# ATSAMD21_board.net
KiCad netlist of a schematic drawn in EAGLE
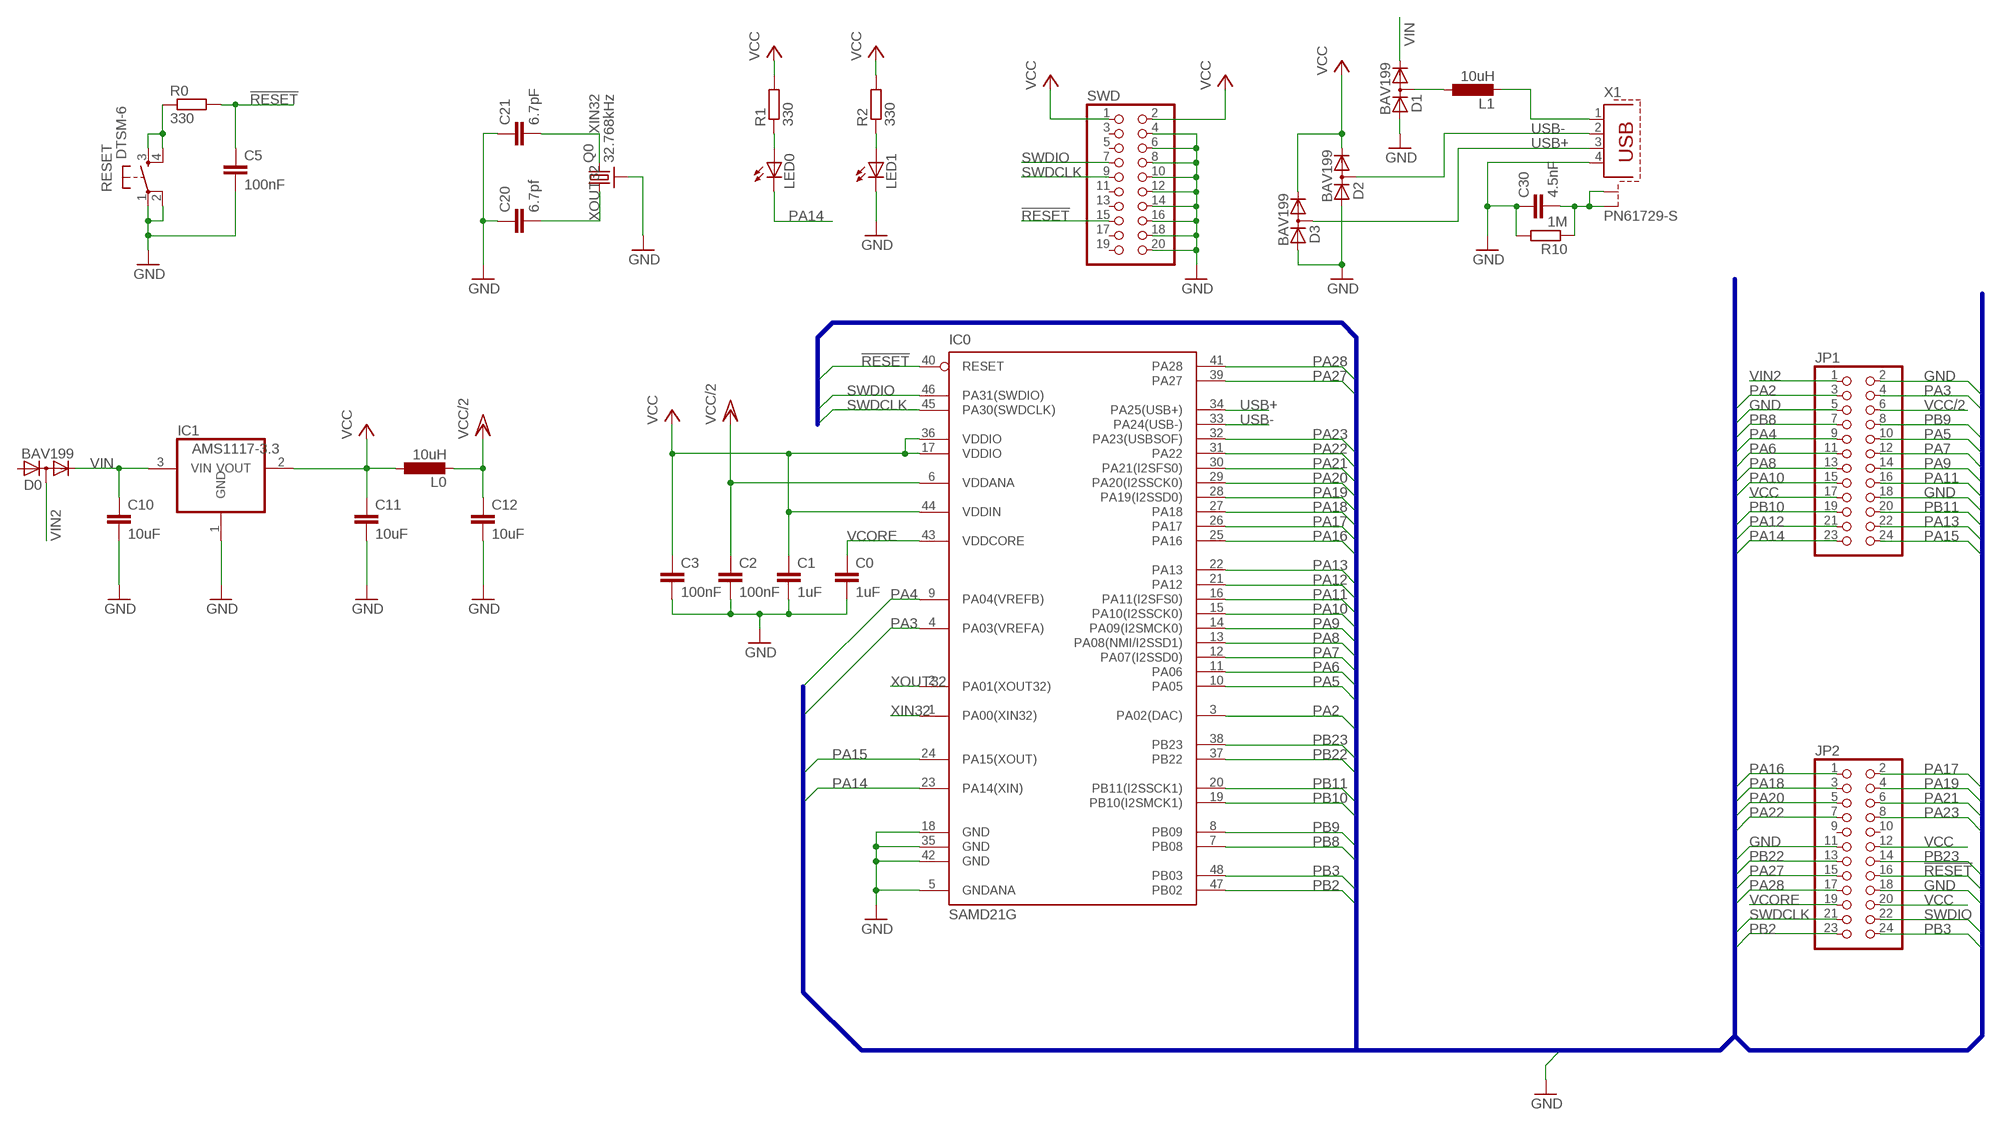
[diagram p0: schematic, sheet 1]

(export (version "E")
  (design (tool "Eeschema 10.0.6"))
  (components
    (comp (ref "C0")
      (value "1uF")
      (footprint "eagle-import:C0805K")
      (libsource (lib "eagle-import") (part "C-EUC0805K"))
    )
    (comp (ref "C1")
      (value "1uF")
      (footprint "eagle-import:C0805K")
      (libsource (lib "eagle-import") (part "C-EUC0805K"))
    )
    (comp (ref "C2")
      (value "100nF")
      (footprint "eagle-import:C0805K")
      (libsource (lib "eagle-import") (part "C-EUC0805K"))
    )
    (comp (ref "C3")
      (value "100nF")
      (footprint "eagle-import:C0805K")
      (libsource (lib "eagle-import") (part "C-EUC0805K"))
    )
    (comp (ref "C5")
      (value "100nF")
      (footprint "eagle-import:C0805K")
      (libsource (lib "eagle-import") (part "C-EUC0805K"))
    )
    (comp (ref "C10")
      (value "10uF")
      (footprint "eagle-import:C0805K")
      (libsource (lib "eagle-import") (part "C-EUC0805K"))
    )
    (comp (ref "C11")
      (value "10uF")
      (footprint "eagle-import:C0805K")
      (libsource (lib "eagle-import") (part "C-EUC0805K"))
    )
    (comp (ref "C12")
      (value "10uF")
      (footprint "eagle-import:C0805K")
      (libsource (lib "eagle-import") (part "C-EUC0805K"))
    )
    (comp (ref "C20")
      (value "6.7pf")
      (footprint "eagle-import:C0805K")
      (libsource (lib "eagle-import") (part "C-EUC0805K"))
    )
    (comp (ref "C21")
      (value "6.7pF")
      (footprint "eagle-import:C0805K")
      (libsource (lib "eagle-import") (part "C-EUC0805K"))
    )
    (comp (ref "C30")
      (value "4.5nF")
      (footprint "eagle-import:C0805K")
      (libsource (lib "eagle-import") (part "C-EUC0805K"))
    )
    (comp (ref "D0")
      (value "BAV199")
      (footprint "eagle-import:SOT23")
      (libsource (lib "eagle-import") (part "BAV199"))
    )
    (comp (ref "D1")
      (value "BAV199")
      (footprint "eagle-import:SOT23")
      (libsource (lib "eagle-import") (part "BAV199"))
    )
    (comp (ref "D2")
      (value "BAV199")
      (footprint "eagle-import:SOT23")
      (libsource (lib "eagle-import") (part "BAV199"))
    )
    (comp (ref "D3")
      (value "BAV199")
      (footprint "eagle-import:SOT23")
      (libsource (lib "eagle-import") (part "BAV199"))
    )
    (comp (ref "IC0")
      (value "SAMD21G")
      (footprint "eagle-import:TQFP48")
      (libsource (lib "eagle-import") (part "SAMD21G"))
    )
    (comp (ref "IC1")
      (value "AMS1117-3.3")
      (footprint "eagle-import:SOT223")
      (fields (field (name "MPN") "REG1117"))
      (libsource (lib "eagle-import") (part "REG1117"))
    )
    (comp (ref "JP1")
      (value "PINHD-2X12")
      (footprint "eagle-import:2X12")
      (libsource (lib "eagle-import") (part "PINHD-2X12"))
    )
    (comp (ref "JP2")
      (value "PINHD-2X12")
      (footprint "eagle-import:2X12")
      (libsource (lib "eagle-import") (part "PINHD-2X12"))
    )
    (comp (ref "L0")
      (value "10uH")
      (footprint "eagle-import:L2012C")
      (libsource (lib "eagle-import") (part "L-EUL2012C"))
    )
    (comp (ref "L1")
      (value "10uH")
      (footprint "eagle-import:L2012C")
      (libsource (lib "eagle-import") (part "L-EUL2012C"))
    )
    (comp (ref "LED0")
      (value "LEDCHIP-LED0805")
      (footprint "eagle-import:CHIP-LED0805")
      (libsource (lib "eagle-import") (part "LEDCHIP-LED0805"))
    )
    (comp (ref "LED1")
      (value "LEDCHIP-LED0805")
      (footprint "eagle-import:CHIP-LED0805")
      (libsource (lib "eagle-import") (part "LEDCHIP-LED0805"))
    )
    (comp (ref "Q0")
      (value "32.768kHz")
      (footprint "eagle-import:TC26H")
      (libsource (lib "eagle-import") (part "CRYSTALTC26H"))
    )
    (comp (ref "R0")
      (value "330")
      (footprint "eagle-import:R0805")
      (libsource (lib "eagle-import") (part "R-EU_R0805"))
    )
    (comp (ref "R1")
      (value "330")
      (footprint "eagle-import:R0805")
      (libsource (lib "eagle-import") (part "R-EU_R0805"))
    )
    (comp (ref "R2")
      (value "330")
      (footprint "eagle-import:R0805")
      (libsource (lib "eagle-import") (part "R-EU_R0805"))
    )
    (comp (ref "R10")
      (value "1M")
      (footprint "eagle-import:R0805")
      (libsource (lib "eagle-import") (part "R-EU_R0805"))
    )
    (comp (ref "RESET")
      (value "DTSM-6")
      (footprint "eagle-import:DTSM-6")
      (libsource (lib "eagle-import") (part "DTSM-6"))
    )
    (comp (ref "SWD")
      (value "PINHD-2X10")
      (footprint "eagle-import:2X10")
      (libsource (lib "eagle-import") (part "PINHD-2X10"))
    )
    (comp (ref "X1")
      (value "PN61729-S")
      (footprint "eagle-import:PN61729-S")
      (libsource (lib "eagle-import") (part "PN61729-S"))
    )
  )
  (nets
    (net (code "1") (name "/PA2") (class "Default")
      (node (ref "IC0") (pin "3") (pinfunction "PA02(DAC)_3") (pintype "bidirectional"))
      (node (ref "JP1") (pin "3") (pinfunction "3_3") (pintype "passive"))
    )
    (net (code "2") (name "/PA3") (class "Default")
      (node (ref "IC0") (pin "4") (pinfunction "PA03(VREFA)_4") (pintype "bidirectional"))
      (node (ref "JP1") (pin "4") (pinfunction "4_4") (pintype "passive"))
    )
    (net (code "3") (name "/PA4") (class "Default")
      (node (ref "IC0") (pin "9") (pinfunction "PA04(VREFB)_9") (pintype "bidirectional"))
      (node (ref "JP1") (pin "9") (pinfunction "9_9") (pintype "passive"))
    )
    (net (code "4") (name "/PA5") (class "Default")
      (node (ref "IC0") (pin "10") (pinfunction "PA05_10") (pintype "bidirectional"))
      (node (ref "JP1") (pin "10") (pinfunction "10_10") (pintype "passive"))
    )
    (net (code "5") (name "/PA6") (class "Default")
      (node (ref "IC0") (pin "11") (pinfunction "PA06_11") (pintype "bidirectional"))
      (node (ref "JP1") (pin "11") (pinfunction "11_11") (pintype "passive"))
    )
    (net (code "6") (name "/PA7") (class "Default")
      (node (ref "IC0") (pin "12") (pinfunction "PA07(I2SSD0)_12") (pintype "bidirectional"))
      (node (ref "JP1") (pin "12") (pinfunction "12_12") (pintype "passive"))
    )
    (net (code "7") (name "/PA8") (class "Default")
      (node (ref "IC0") (pin "13") (pinfunction "PA08(NMI/I2SSD1)_13") (pintype "bidirectional"))
      (node (ref "JP1") (pin "13") (pinfunction "13_13") (pintype "passive"))
    )
    (net (code "8") (name "/PA9") (class "Default")
      (node (ref "IC0") (pin "14") (pinfunction "PA09(I2SMCK0)_14") (pintype "bidirectional"))
      (node (ref "JP1") (pin "14") (pinfunction "14_14") (pintype "passive"))
    )
    (net (code "9") (name "/PA10") (class "Default")
      (node (ref "IC0") (pin "15") (pinfunction "PA10(I2SSCK0)_15") (pintype "bidirectional"))
      (node (ref "JP1") (pin "15") (pinfunction "15_15") (pintype "passive"))
    )
    (net (code "10") (name "/PA11") (class "Default")
      (node (ref "IC0") (pin "16") (pinfunction "PA11(I2SFS0)_16") (pintype "bidirectional"))
      (node (ref "JP1") (pin "16") (pinfunction "16_16") (pintype "passive"))
    )
    (net (code "11") (name "/PA12") (class "Default")
      (node (ref "IC0") (pin "21") (pinfunction "PA12_21") (pintype "bidirectional"))
      (node (ref "JP1") (pin "21") (pinfunction "21_21") (pintype "passive"))
    )
    (net (code "12") (name "/PA13") (class "Default")
      (node (ref "IC0") (pin "22") (pinfunction "PA13_22") (pintype "bidirectional"))
      (node (ref "JP1") (pin "22") (pinfunction "22_22") (pintype "passive"))
    )
    (net (code "13") (name "/PA14") (class "Default")
      (node (ref "IC0") (pin "23") (pinfunction "PA14(XIN)_23") (pintype "bidirectional"))
      (node (ref "JP1") (pin "23") (pinfunction "23_23") (pintype "passive"))
      (node (ref "LED0") (pin "C") (pinfunction "C_C") (pintype "passive"))
    )
    (net (code "14") (name "/PA15") (class "Default")
      (node (ref "IC0") (pin "24") (pinfunction "PA15(XOUT)_24") (pintype "bidirectional"))
      (node (ref "JP1") (pin "24") (pinfunction "24_24") (pintype "passive"))
    )
    (net (code "15") (name "/PA16") (class "Default")
      (node (ref "IC0") (pin "25") (pinfunction "PA16_25") (pintype "bidirectional"))
      (node (ref "JP2") (pin "1") (pinfunction "1_1") (pintype "passive"))
    )
    (net (code "16") (name "/PA17") (class "Default")
      (node (ref "IC0") (pin "26") (pinfunction "PA17_26") (pintype "bidirectional"))
      (node (ref "JP2") (pin "2") (pinfunction "2_2") (pintype "passive"))
    )
    (net (code "17") (name "/PA18") (class "Default")
      (node (ref "IC0") (pin "27") (pinfunction "PA18_27") (pintype "bidirectional"))
      (node (ref "JP2") (pin "3") (pinfunction "3_3") (pintype "passive"))
    )
    (net (code "18") (name "/PA19") (class "Default")
      (node (ref "IC0") (pin "28") (pinfunction "PA19(I2SSD0)_28") (pintype "bidirectional"))
      (node (ref "JP2") (pin "4") (pinfunction "4_4") (pintype "passive"))
    )
    (net (code "19") (name "/PA20") (class "Default")
      (node (ref "IC0") (pin "29") (pinfunction "PA20(I2SSCK0)_29") (pintype "bidirectional"))
      (node (ref "JP2") (pin "5") (pinfunction "5_5") (pintype "passive"))
    )
    (net (code "20") (name "/PA21") (class "Default")
      (node (ref "IC0") (pin "30") (pinfunction "PA21(I2SFS0)_30") (pintype "bidirectional"))
      (node (ref "JP2") (pin "6") (pinfunction "6_6") (pintype "passive"))
    )
    (net (code "21") (name "/PA22") (class "Default")
      (node (ref "IC0") (pin "31") (pinfunction "PA22_31") (pintype "bidirectional"))
      (node (ref "JP2") (pin "7") (pinfunction "7_7") (pintype "passive"))
    )
    (net (code "22") (name "/PA23") (class "Default")
      (node (ref "IC0") (pin "32") (pinfunction "PA23(USBSOF)_32") (pintype "bidirectional"))
      (node (ref "JP2") (pin "8") (pinfunction "8_8") (pintype "passive"))
    )
    (net (code "23") (name "/PA27") (class "Default")
      (node (ref "IC0") (pin "39") (pinfunction "PA27_39") (pintype "bidirectional"))
      (node (ref "JP2") (pin "15") (pinfunction "15_15") (pintype "passive"))
    )
    (net (code "24") (name "/PA28") (class "Default")
      (node (ref "IC0") (pin "41") (pinfunction "PA28_41") (pintype "bidirectional"))
      (node (ref "JP2") (pin "17") (pinfunction "17_17") (pintype "passive"))
    )
    (net (code "25") (name "/PB2") (class "Default")
      (node (ref "IC0") (pin "47") (pinfunction "PB02_47") (pintype "bidirectional"))
      (node (ref "JP2") (pin "23") (pinfunction "23_23") (pintype "passive"))
    )
    (net (code "26") (name "/PB3") (class "Default")
      (node (ref "IC0") (pin "48") (pinfunction "PB03_48") (pintype "bidirectional"))
      (node (ref "JP2") (pin "24") (pinfunction "24_24") (pintype "passive"))
    )
    (net (code "27") (name "/PB8") (class "Default")
      (node (ref "IC0") (pin "7") (pinfunction "PB08_7") (pintype "bidirectional"))
      (node (ref "JP1") (pin "7") (pinfunction "7_7") (pintype "passive"))
    )
    (net (code "28") (name "/PB9") (class "Default")
      (node (ref "IC0") (pin "8") (pinfunction "PB09_8") (pintype "bidirectional"))
      (node (ref "JP1") (pin "8") (pinfunction "8_8") (pintype "passive"))
    )
    (net (code "29") (name "/PB10") (class "Default")
      (node (ref "IC0") (pin "19") (pinfunction "PB10(I2SMCK1)_19") (pintype "bidirectional"))
      (node (ref "JP1") (pin "19") (pinfunction "19_19") (pintype "passive"))
    )
    (net (code "30") (name "/PB11") (class "Default")
      (node (ref "IC0") (pin "20") (pinfunction "PB11(I2SSCK1)_20") (pintype "bidirectional"))
      (node (ref "JP1") (pin "20") (pinfunction "20_20") (pintype "passive"))
    )
    (net (code "31") (name "/PB22") (class "Default")
      (node (ref "IC0") (pin "37") (pinfunction "PB22_37") (pintype "bidirectional"))
      (node (ref "JP2") (pin "13") (pinfunction "13_13") (pintype "passive"))
    )
    (net (code "32") (name "/PB23") (class "Default")
      (node (ref "IC0") (pin "38") (pinfunction "PB23_38") (pintype "bidirectional"))
      (node (ref "JP2") (pin "14") (pinfunction "14_14") (pintype "passive"))
    )
    (net (code "33") (name "/SWDCLK") (class "Default")
      (node (ref "IC0") (pin "45") (pinfunction "PA30(SWDCLK)_45") (pintype "bidirectional"))
      (node (ref "JP2") (pin "21") (pinfunction "21_21") (pintype "passive"))
      (node (ref "SWD") (pin "9") (pinfunction "9_9") (pintype "passive"))
    )
    (net (code "34") (name "/SWDIO") (class "Default")
      (node (ref "IC0") (pin "46") (pinfunction "PA31(SWDIO)_46") (pintype "bidirectional"))
      (node (ref "JP2") (pin "22") (pinfunction "22_22") (pintype "passive"))
      (node (ref "SWD") (pin "7") (pinfunction "7_7") (pintype "passive"))
    )
    (net (code "35") (name "/USB+") (class "Default")
      (node (ref "D3") (pin "3") (pinfunction "AC_3") (pintype "passive"))
      (node (ref "IC0") (pin "34") (pinfunction "PA25(USB+)_34") (pintype "bidirectional"))
      (node (ref "X1") (pin "3") (pinfunction "3_3") (pintype "passive"))
    )
    (net (code "36") (name "/USB-") (class "Default")
      (node (ref "D2") (pin "3") (pinfunction "AC_3") (pintype "passive"))
      (node (ref "IC0") (pin "33") (pinfunction "PA24(USB-)_33") (pintype "bidirectional"))
      (node (ref "X1") (pin "2") (pinfunction "2_2") (pintype "passive"))
    )
    (net (code "37") (name "/VCORE") (class "Default")
      (node (ref "C0") (pin "1") (pinfunction "1_1") (pintype "passive"))
      (node (ref "IC0") (pin "43") (pinfunction "VDDCORE_43") (pintype "power_in"))
      (node (ref "JP2") (pin "19") (pinfunction "19_19") (pintype "passive"))
    )
    (net (code "38") (name "/VIN") (class "Default")
      (node (ref "C10") (pin "1") (pinfunction "1_1") (pintype "passive"))
      (node (ref "D0") (pin "2") (pinfunction "C_2") (pintype "passive"))
      (node (ref "D1") (pin "2") (pinfunction "C_2") (pintype "passive"))
      (node (ref "IC1") (pin "3") (pinfunction "VIN_3") (pintype "input"))
    )
    (net (code "39") (name "/VIN2") (class "Default")
      (node (ref "D0") (pin "3") (pinfunction "AC_3") (pintype "passive"))
      (node (ref "JP1") (pin "1") (pinfunction "1_1") (pintype "passive"))
    )
    (net (code "40") (name "/XIN32") (class "Default")
      (node (ref "C21") (pin "2") (pinfunction "2_2") (pintype "passive"))
      (node (ref "IC0") (pin "1") (pinfunction "PA00(XIN32)_1") (pintype "bidirectional"))
      (node (ref "Q0") (pin "2") (pinfunction "2_2") (pintype "passive"))
    )
    (net (code "41") (name "/XOUT32") (class "Default")
      (node (ref "C20") (pin "2") (pinfunction "2_2") (pintype "passive"))
      (node (ref "IC0") (pin "2") (pinfunction "PA01(XOUT32)_2") (pintype "bidirectional"))
      (node (ref "Q0") (pin "1") (pinfunction "1_1") (pintype "passive"))
    )
    (net (code "42") (name "/~{RESET}") (class "Default")
      (node (ref "C5") (pin "1") (pinfunction "1_1") (pintype "passive"))
      (node (ref "IC0") (pin "40") (pinfunction "RESET_40") (pintype "bidirectional"))
      (node (ref "JP2") (pin "16") (pinfunction "16_16") (pintype "passive"))
      (node (ref "R0") (pin "2") (pinfunction "2_2") (pintype "passive"))
      (node (ref "SWD") (pin "15") (pinfunction "15_15") (pintype "passive"))
    )
    (net (code "43") (name "GND") (class "Default")
      (node (ref "C0") (pin "2") (pinfunction "2_2") (pintype "passive"))
      (node (ref "C1") (pin "2") (pinfunction "2_2") (pintype "passive"))
      (node (ref "C10") (pin "2") (pinfunction "2_2") (pintype "passive"))
      (node (ref "C11") (pin "2") (pinfunction "2_2") (pintype "passive"))
      (node (ref "C12") (pin "2") (pinfunction "2_2") (pintype "passive"))
      (node (ref "C2") (pin "2") (pinfunction "2_2") (pintype "passive"))
      (node (ref "C20") (pin "1") (pinfunction "1_1") (pintype "passive"))
      (node (ref "C21") (pin "1") (pinfunction "1_1") (pintype "passive"))
      (node (ref "C3") (pin "2") (pinfunction "2_2") (pintype "passive"))
      (node (ref "C30") (pin "1") (pinfunction "1_1") (pintype "passive"))
      (node (ref "C5") (pin "2") (pinfunction "2_2") (pintype "passive"))
      (node (ref "D1") (pin "1") (pinfunction "A_1") (pintype "passive"))
      (node (ref "D2") (pin "1") (pinfunction "A_1") (pintype "passive"))
      (node (ref "D3") (pin "1") (pinfunction "A_1") (pintype "passive"))
      (node (ref "IC0") (pin "18") (pinfunction "GND_18") (pintype "power_in"))
      (node (ref "IC0") (pin "35") (pinfunction "GND_35") (pintype "power_in"))
      (node (ref "IC0") (pin "42") (pinfunction "GND_42") (pintype "power_in"))
      (node (ref "IC0") (pin "5") (pinfunction "GNDANA_5") (pintype "power_in"))
      (node (ref "IC1") (pin "1") (pinfunction "GND_1") (pintype "power_in"))
      (node (ref "JP1") (pin "18") (pinfunction "18_18") (pintype "passive"))
      (node (ref "JP1") (pin "2") (pinfunction "2_2") (pintype "passive"))
      (node (ref "JP1") (pin "5") (pinfunction "5_5") (pintype "passive"))
      (node (ref "JP2") (pin "11") (pinfunction "11_11") (pintype "passive"))
      (node (ref "JP2") (pin "18") (pinfunction "18_18") (pintype "passive"))
      (node (ref "LED1") (pin "C") (pinfunction "C_C") (pintype "passive"))
      (node (ref "Q0") (pin "P$1") (pinfunction "3_P$1") (pintype "passive"))
      (node (ref "R10") (pin "2") (pinfunction "2_2") (pintype "passive"))
      (node (ref "RESET") (pin "1") (pinfunction "1_1") (pintype "passive"))
      (node (ref "RESET") (pin "2") (pinfunction "2_2") (pintype "passive"))
      (node (ref "SWD") (pin "10") (pinfunction "10_10") (pintype "passive"))
      (node (ref "SWD") (pin "12") (pinfunction "12_12") (pintype "passive"))
      (node (ref "SWD") (pin "14") (pinfunction "14_14") (pintype "passive"))
      (node (ref "SWD") (pin "16") (pinfunction "16_16") (pintype "passive"))
      (node (ref "SWD") (pin "18") (pinfunction "18_18") (pintype "passive"))
      (node (ref "SWD") (pin "20") (pinfunction "20_20") (pintype "passive"))
      (node (ref "SWD") (pin "4") (pinfunction "4_4") (pintype "passive"))
      (node (ref "SWD") (pin "6") (pinfunction "6_6") (pintype "passive"))
      (node (ref "SWD") (pin "8") (pinfunction "8_8") (pintype "passive"))
      (node (ref "X1") (pin "4") (pinfunction "4_4") (pintype "passive"))
    )
    (net (code "44") (name "Net-(C30-Pad2)") (class "Default")
      (node (ref "C30") (pin "2") (pinfunction "2_2") (pintype "passive"))
      (node (ref "R10") (pin "1") (pinfunction "1_1") (pintype "passive"))
      (node (ref "X1") (pin "S1") (pinfunction "S1_S1") (pintype "passive"))
      (node (ref "X1") (pin "S2") (pinfunction "S2_S2") (pintype "passive"))
    )
    (net (code "45") (name "Net-(D1-AC)") (class "Default")
      (node (ref "D1") (pin "3") (pinfunction "AC_3") (pintype "passive"))
      (node (ref "L1") (pin "1") (pinfunction "1_1") (pintype "passive"))
    )
    (net (code "46") (name "Net-(L1-Pad2)") (class "Default")
      (node (ref "L1") (pin "2") (pinfunction "2_2") (pintype "passive"))
      (node (ref "X1") (pin "1") (pinfunction "1_1") (pintype "passive"))
    )
    (net (code "47") (name "Net-(LED0-PadA)") (class "Default")
      (node (ref "LED0") (pin "A") (pinfunction "A_A") (pintype "passive"))
      (node (ref "R1") (pin "1") (pinfunction "1_1") (pintype "passive"))
    )
    (net (code "48") (name "Net-(LED1-PadA)") (class "Default")
      (node (ref "LED1") (pin "A") (pinfunction "A_A") (pintype "passive"))
      (node (ref "R2") (pin "1") (pinfunction "1_1") (pintype "passive"))
    )
    (net (code "49") (name "Net-(R0-Pad1)") (class "Default")
      (node (ref "R0") (pin "1") (pinfunction "1_1") (pintype "passive"))
      (node (ref "RESET") (pin "3") (pinfunction "3_3") (pintype "passive"))
      (node (ref "RESET") (pin "4") (pinfunction "4_4") (pintype "passive"))
    )
    (net (code "50") (name "VCC") (class "Default")
      (node (ref "C1") (pin "1") (pinfunction "1_1") (pintype "passive"))
      (node (ref "C11") (pin "1") (pinfunction "1_1") (pintype "passive"))
      (node (ref "C3") (pin "1") (pinfunction "1_1") (pintype "passive"))
      (node (ref "D2") (pin "2") (pinfunction "C_2") (pintype "passive"))
      (node (ref "D3") (pin "2") (pinfunction "C_2") (pintype "passive"))
      (node (ref "IC0") (pin "17") (pinfunction "VDDIO_17") (pintype "power_in"))
      (node (ref "IC0") (pin "36") (pinfunction "VDDIO_36") (pintype "power_in"))
      (node (ref "IC0") (pin "44") (pinfunction "VDDIN_44") (pintype "power_in"))
      (node (ref "IC1") (pin "2") (pinfunction "VOUT_2") (pintype "output"))
      (node (ref "JP1") (pin "17") (pinfunction "17_17") (pintype "passive"))
      (node (ref "JP2") (pin "12") (pinfunction "12_12") (pintype "passive"))
      (node (ref "JP2") (pin "20") (pinfunction "20_20") (pintype "passive"))
      (node (ref "L0") (pin "1") (pinfunction "1_1") (pintype "passive"))
      (node (ref "R1") (pin "2") (pinfunction "2_2") (pintype "passive"))
      (node (ref "R2") (pin "2") (pinfunction "2_2") (pintype "passive"))
      (node (ref "SWD") (pin "1") (pinfunction "1_1") (pintype "passive"))
      (node (ref "SWD") (pin "2") (pinfunction "2_2") (pintype "passive"))
    )
    (net (code "51") (name "VCC{slash}2") (class "Default")
      (node (ref "C12") (pin "1") (pinfunction "1_1") (pintype "passive"))
      (node (ref "C2") (pin "1") (pinfunction "1_1") (pintype "passive"))
      (node (ref "IC0") (pin "6") (pinfunction "VDDANA_6") (pintype "power_in"))
      (node (ref "JP1") (pin "6") (pinfunction "6_6") (pintype "passive"))
      (node (ref "L0") (pin "2") (pinfunction "2_2") (pintype "passive"))
    )
    (net (code "52") (name "unconnected-(D0-A-Pad1)") (class "Default")
      (node (ref "D0") (pin "1") (pinfunction "A_1") (pintype "passive"))
    )
    (net (code "53") (name "unconnected-(JP2-Pad9)") (class "Default")
      (node (ref "JP2") (pin "9") (pinfunction "9_9") (pintype "passive"))
    )
    (net (code "54") (name "unconnected-(JP2-Pad10)") (class "Default")
      (node (ref "JP2") (pin "10") (pinfunction "10_10") (pintype "passive"))
    )
    (net (code "55") (name "unconnected-(SWD-Pad3)") (class "Default")
      (node (ref "SWD") (pin "3") (pinfunction "3_3") (pintype "passive"))
    )
    (net (code "56") (name "unconnected-(SWD-Pad5)") (class "Default")
      (node (ref "SWD") (pin "5") (pinfunction "5_5") (pintype "passive"))
    )
    (net (code "57") (name "unconnected-(SWD-Pad11)") (class "Default")
      (node (ref "SWD") (pin "11") (pinfunction "11_11") (pintype "passive"))
    )
    (net (code "58") (name "unconnected-(SWD-Pad13)") (class "Default")
      (node (ref "SWD") (pin "13") (pinfunction "13_13") (pintype "passive"))
    )
    (net (code "59") (name "unconnected-(SWD-Pad17)") (class "Default")
      (node (ref "SWD") (pin "17") (pinfunction "17_17") (pintype "passive"))
    )
    (net (code "60") (name "unconnected-(SWD-Pad19)") (class "Default")
      (node (ref "SWD") (pin "19") (pinfunction "19_19") (pintype "passive"))
    )
  )
)
